# KMO_IO_MV2_9_mout.net
KiCad netlist of a schematic drawn in EAGLE
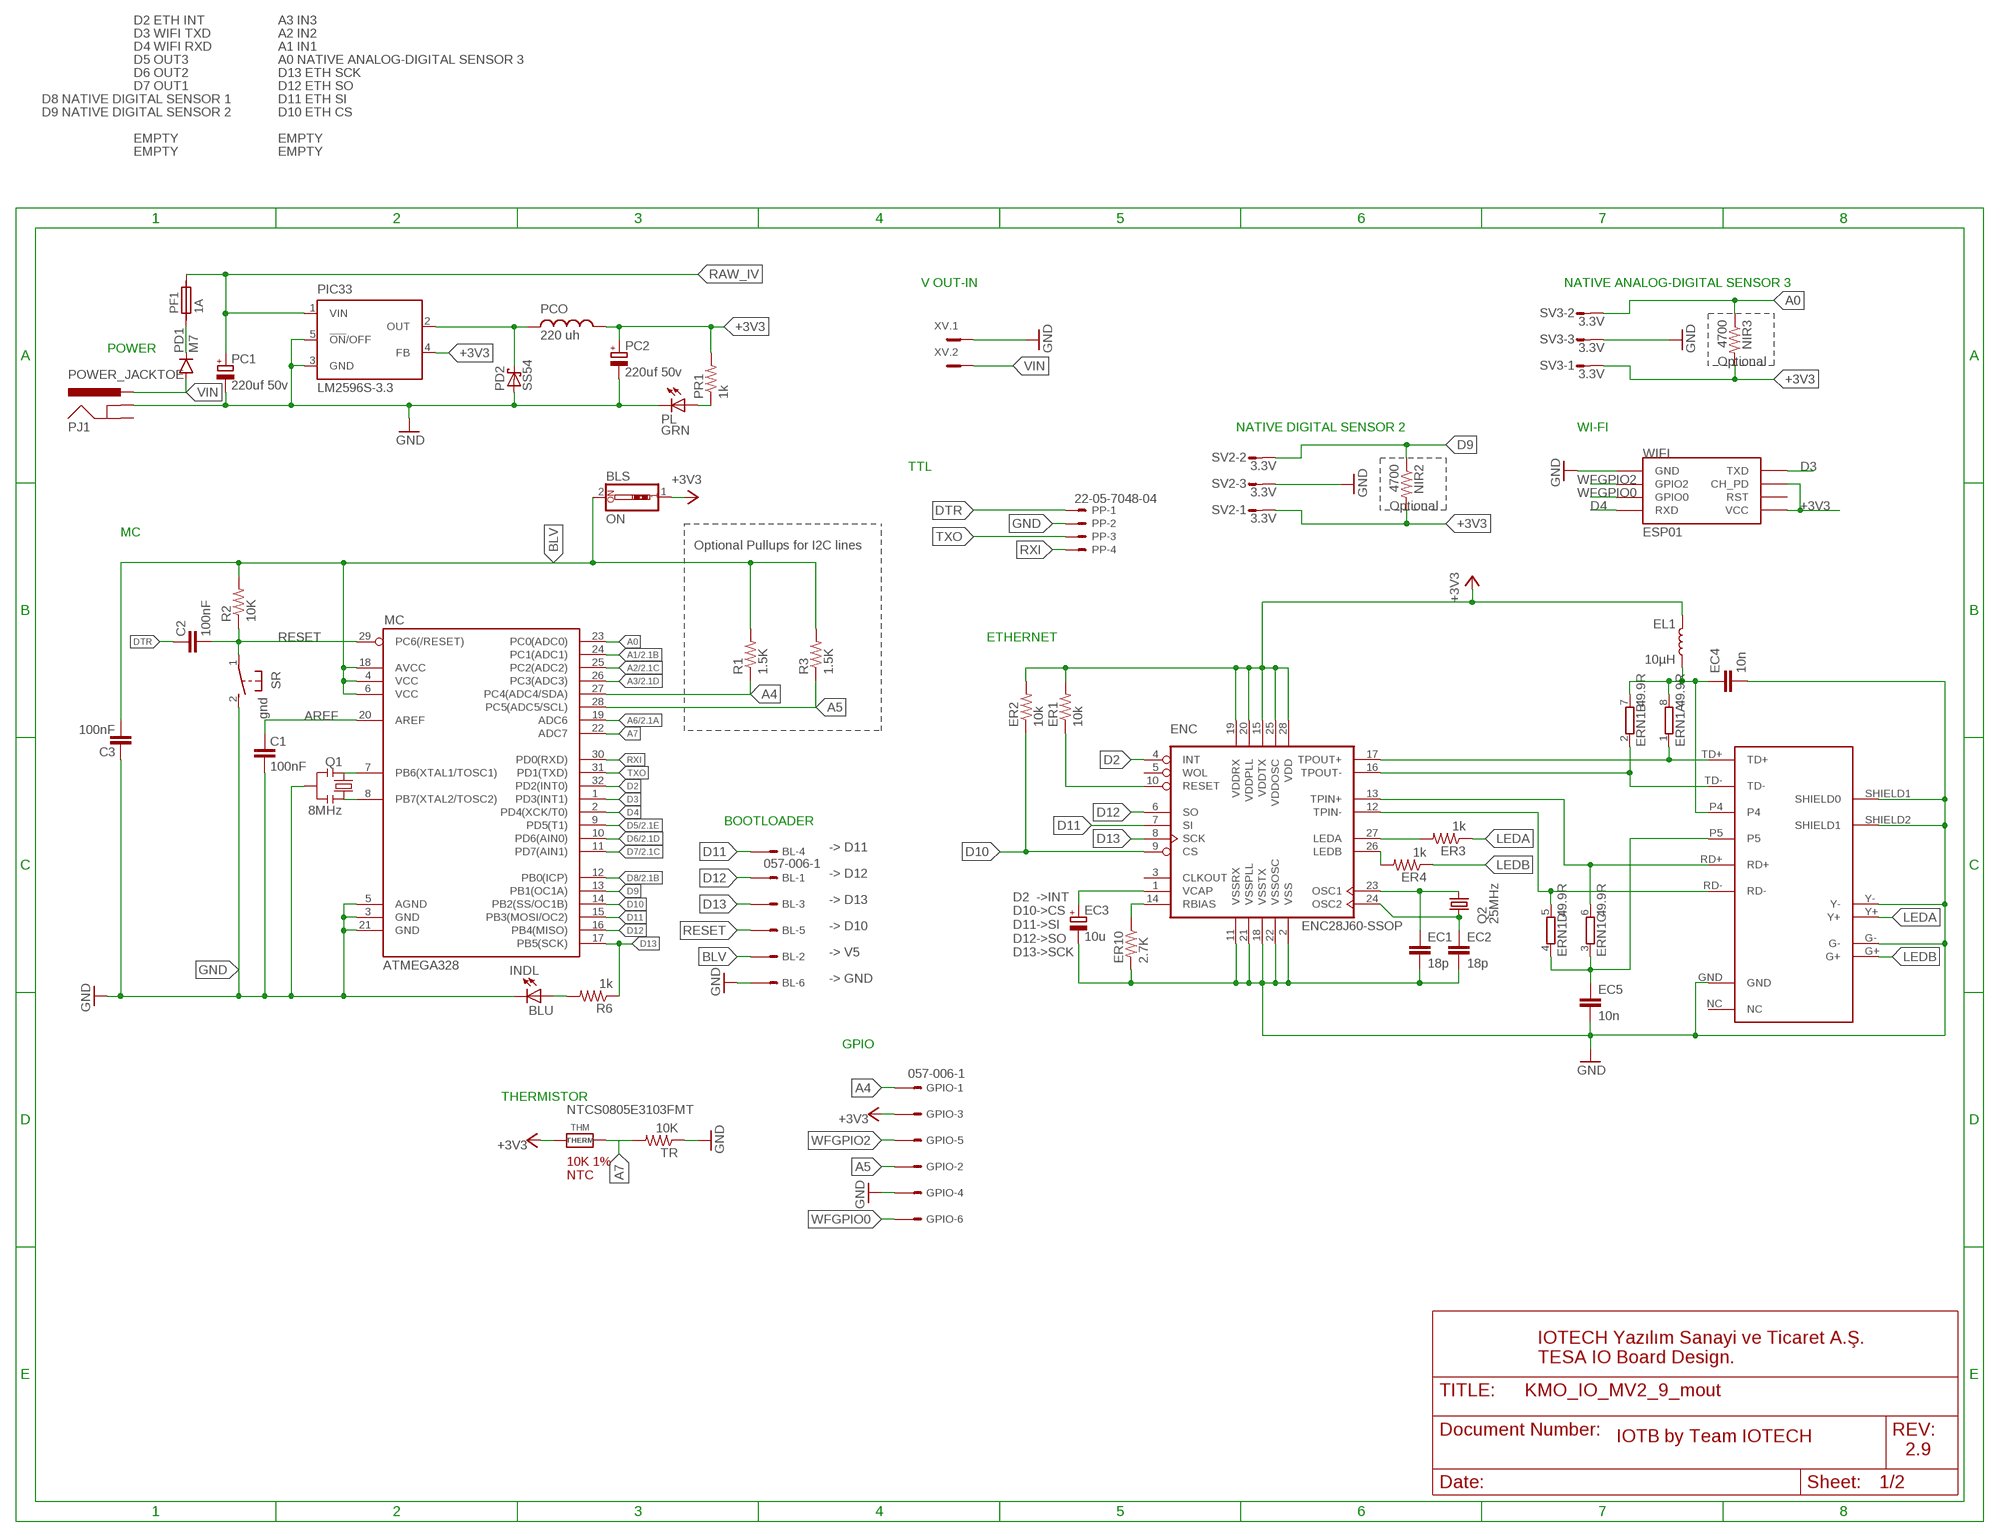
[diagram p0: schematic, sheet 1]
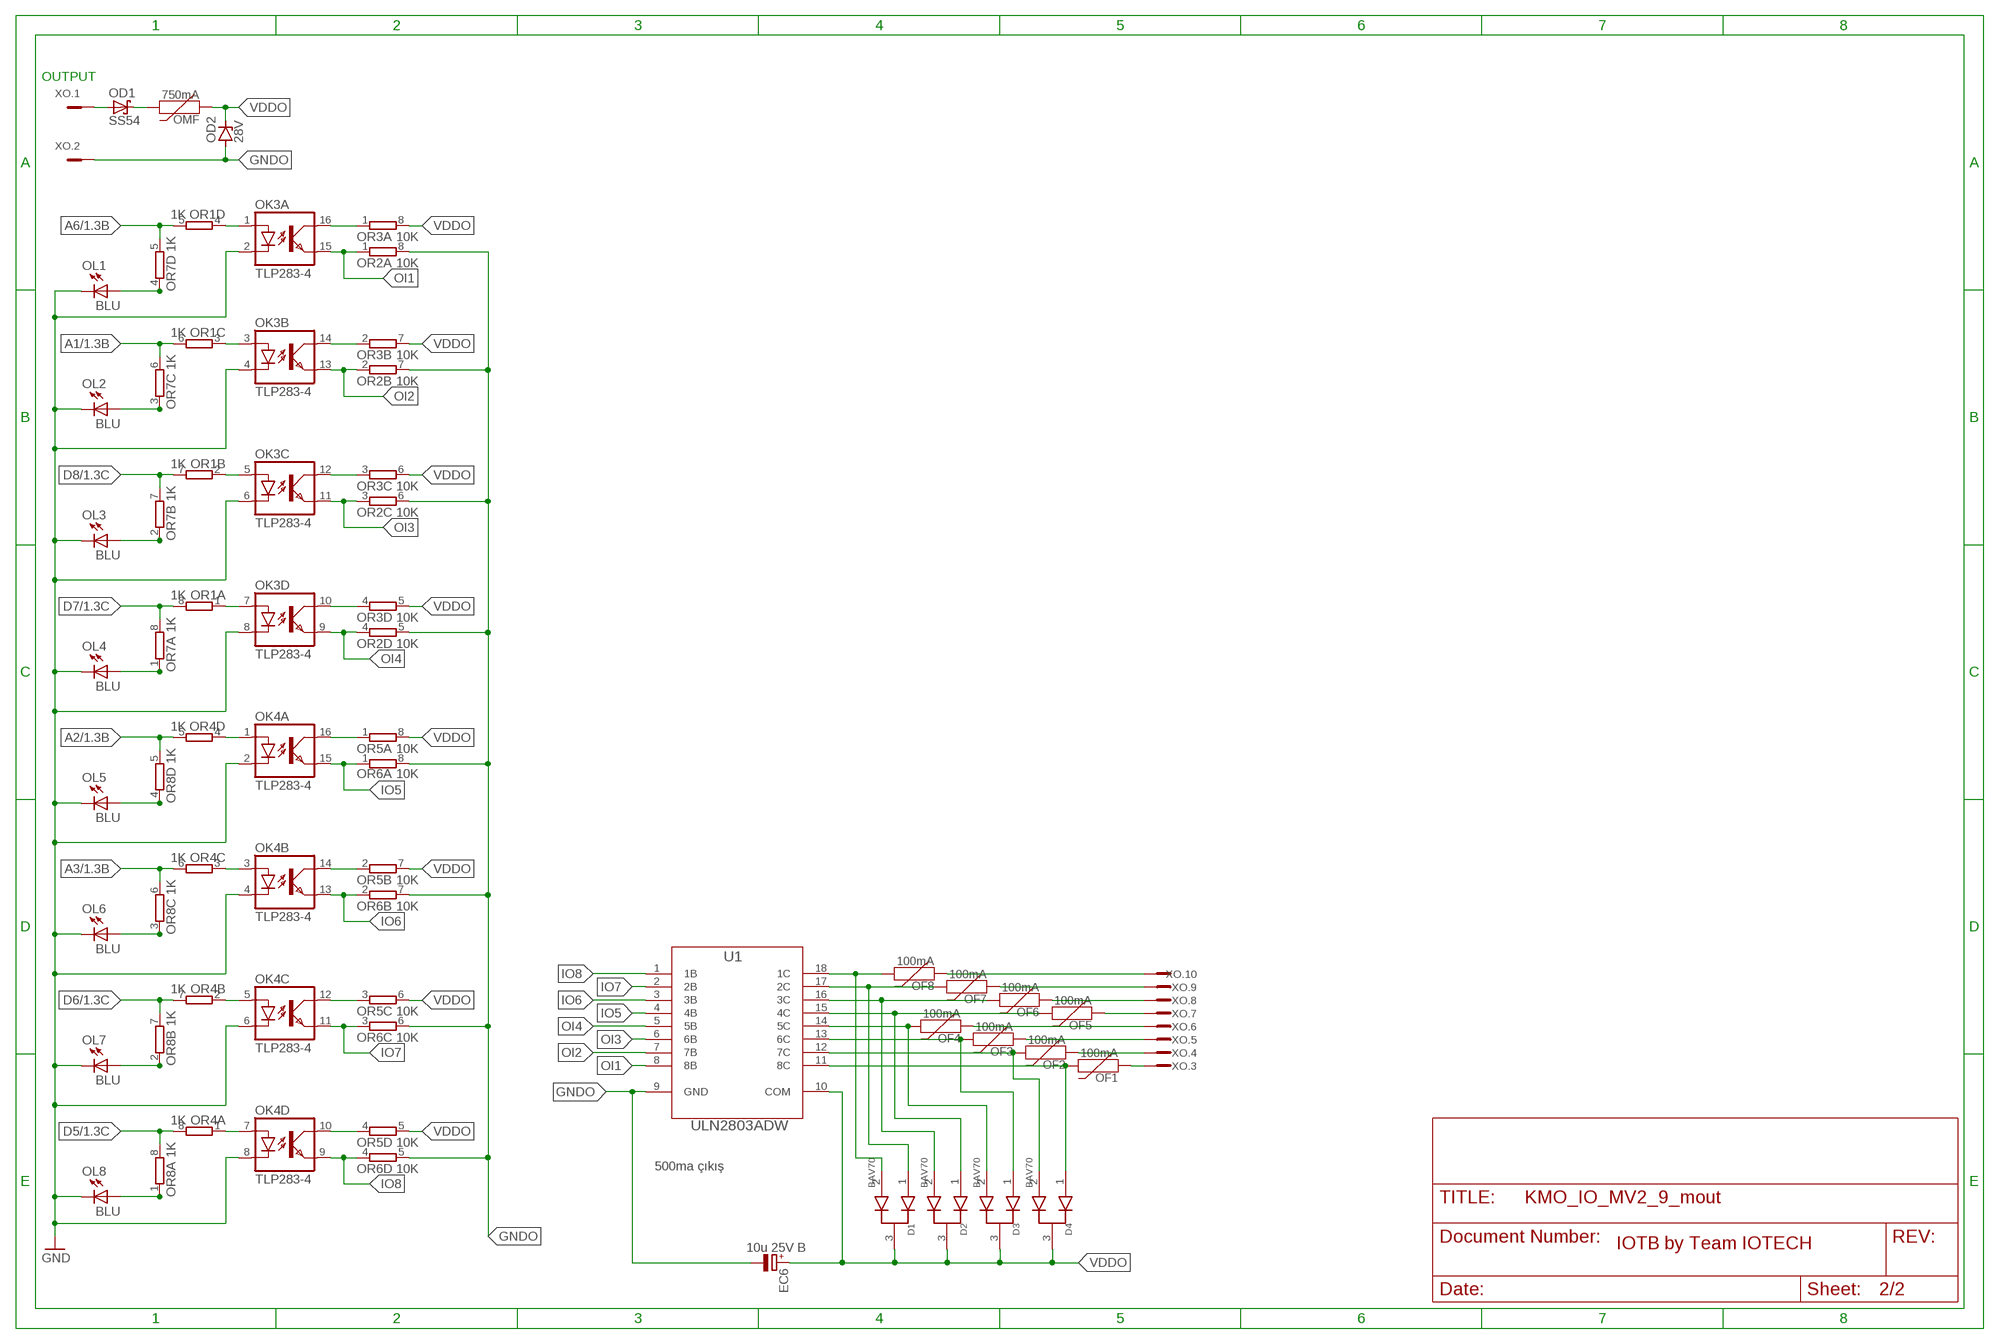
[diagram p1: schematic, sheet 2]

(export (version "E")
  (design (tool "Eeschema 10.0.6"))
  (components
    (comp (ref "BL")
      (value "057-006-1")
      (footprint "eagle-import:057-006-1")
      (libsource (lib "eagle-import") (part "057-006-1"))
    )
    (comp (ref "BLS")
      (value "ON")
      (footprint "eagle-import:EDG-01")
      (libsource (lib "eagle-import") (part "SW_DIP-1"))
    )
    (comp (ref "C1")
      (value "100nF")
      (footprint "eagle-import:0805")
      (libsource (lib "eagle-import") (part "CAP0805"))
    )
    (comp (ref "C2")
      (value "100nF")
      (footprint "eagle-import:0805")
      (libsource (lib "eagle-import") (part "CAP0805"))
    )
    (comp (ref "C3")
      (value "100nF")
      (footprint "eagle-import:0805")
      (libsource (lib "eagle-import") (part "CAP0805"))
    )
    (comp (ref "EC1")
      (value "18p")
      (footprint "eagle-import:0805")
      (libsource (lib "eagle-import") (part "CAP0805"))
    )
    (comp (ref "EC2")
      (value "18p")
      (footprint "eagle-import:0805")
      (libsource (lib "eagle-import") (part "CAP0805"))
    )
    (comp (ref "EC3")
      (value "10u")
      (footprint "eagle-import:CT3216")
      (libsource (lib "eagle-import") (part "CPOL-EUCT3216"))
    )
    (comp (ref "EC4")
      (value "10n")
      (footprint "eagle-import:0805")
      (libsource (lib "eagle-import") (part "CAP0805"))
    )
    (comp (ref "EC5")
      (value "10n")
      (footprint "eagle-import:0805")
      (libsource (lib "eagle-import") (part "CAP0805"))
    )
    (comp (ref "EL1")
      (value "10µH")
      (footprint "eagle-import:0805")
      (libsource (lib "eagle-import") (part "INDUCTOR-0805-3.3UH"))
    )
    (comp (ref "ENC")
      (value "ENC28J60-SSOP")
      (footprint "eagle-import:SSOP28")
      (libsource (lib "eagle-import") (part "ENC28J60-SSOP"))
    )
    (comp (ref "ER1")
      (value "10k")
      (footprint "eagle-import:0805")
      (libsource (lib "eagle-import") (part "RESISTOR0805-RES"))
    )
    (comp (ref "ER2")
      (value "10k")
      (footprint "eagle-import:0805")
      (libsource (lib "eagle-import") (part "RESISTOR0805-RES"))
    )
    (comp (ref "ER3")
      (value "1k")
      (footprint "eagle-import:0805")
      (libsource (lib "eagle-import") (part "RESISTOR0805-RES"))
    )
    (comp (ref "ER4")
      (value "1k")
      (footprint "eagle-import:0805")
      (libsource (lib "eagle-import") (part "RESISTOR0805-RES"))
    )
    (comp (ref "ER10")
      (value "2.7K")
      (footprint "eagle-import:0805")
      (libsource (lib "eagle-import") (part "RESISTOR0805-RES"))
    )
    (comp (ref "ERN1")
      (value "49.9R")
      (footprint "eagle-import:0603-ARV")
      (libsource (lib "eagle-import") (part "4R-N0603-ARV"))
    )
    (comp (ref "GPIO")
      (value "057-006-1")
      (footprint "eagle-import:057-006-1")
      (libsource (lib "eagle-import") (part "057-006-1"))
    )
    (comp (ref "INDL")
      (value "BLU")
      (footprint "eagle-import:CHIP-LED0805")
      (libsource (lib "eagle-import") (part "LEDCHIP-LED0805"))
    )
    (comp (ref "MC")
      (value "ATMEGA328")
      (footprint "eagle-import:TQFP32-08")
      (libsource (lib "eagle-import") (part "ATMEGA168"))
    )
    (comp (ref "NIR2")
      (value "4700")
      (footprint "eagle-import:0805")
      (libsource (lib "eagle-import") (part "RESISTOR0805-RES"))
    )
    (comp (ref "NIR3")
      (value "4700")
      (footprint "eagle-import:0805")
      (libsource (lib "eagle-import") (part "RESISTOR0805-RES"))
    )
    (comp (ref "PC1")
      (value "220uf 50v")
      (footprint "eagle-import:140CLH-1010")
      (libsource (lib "eagle-import") (part "CPOL-EU140CLH-1010"))
    )
    (comp (ref "PC2")
      (value "220uf 50v")
      (footprint "eagle-import:140CLH-1010")
      (libsource (lib "eagle-import") (part "CPOL-EU140CLH-1010"))
    )
    (comp (ref "PCO")
      (value "220 uh")
      (footprint "eagle-import:MSS1260")
      (libsource (lib "eagle-import") (part "MSS1260"))
    )
    (comp (ref "PD1")
      (value "M7")
      (footprint "eagle-import:SMA-DIODE")
      (libsource (lib "eagle-import") (part "DIODESMA"))
    )
    (comp (ref "PD2")
      (value "SS54")
      (footprint "eagle-import:SMB")
      (libsource (lib "eagle-import") (part "SCHOTTKY-DIODESMD"))
    )
    (comp (ref "PF1")
      (value "1A")
      (footprint "eagle-import:1820")
      (libsource (lib "eagle-import") (part "SIBA194600"))
    )
    (comp (ref "PIC33")
      (value "LM2596S-3.3")
      (footprint "eagle-import:TO263-5")
      (fields
        (field (name "MF") "NATIONAL SEMICONDUCTOR")
        (field (name "MPN") "LM2596S-ADJ/NOPB")
        (field (name "SPICEPREFIX") "X")
      )
      (libsource (lib "eagle-import") (part "LM2596S"))
    )
    (comp (ref "PJ1")
      (value "POWER_JACKTOE")
      (footprint "eagle-import:POWER_JACK_SMD_OVERPASTE_TOE")
      (libsource (lib "eagle-import") (part "POWER_JACKTOE"))
    )
    (comp (ref "PL")
      (value "GRN")
      (footprint "eagle-import:CHIP-LED0805")
      (libsource (lib "eagle-import") (part "LEDCHIP-LED0805"))
    )
    (comp (ref "PP")
      (value "22-05-7048-04")
      (footprint "eagle-import:7395-04")
      (fields (field (name "MF") "MOLEX"))
      (libsource (lib "eagle-import") (part "22-?-0405-7048"))
    )
    (comp (ref "PR1")
      (value "1k")
      (footprint "eagle-import:0805")
      (libsource (lib "eagle-import") (part "RESISTOR0805-RES"))
    )
    (comp (ref "Q1")
      (value "8MHz")
      (footprint "eagle-import:RESONATOR-SMD-1_1")
      (libsource (lib "eagle-import") (part "RESONATOR1{colon}1"))
    )
    (comp (ref "Q2")
      (value "25MHz")
      (footprint "eagle-import:5.0X3.2_2")
      (libsource (lib "eagle-import") (part "KX-9B"))
    )
    (comp (ref "R1")
      (value "1.5K")
      (footprint "eagle-import:0805")
      (libsource (lib "eagle-import") (part "RESISTOR0805-RES"))
    )
    (comp (ref "R2")
      (value "10K")
      (footprint "eagle-import:0805")
      (libsource (lib "eagle-import") (part "RESISTOR0805-RES"))
    )
    (comp (ref "R3")
      (value "1.5K")
      (footprint "eagle-import:0805")
      (libsource (lib "eagle-import") (part "RESISTOR0805-RES"))
    )
    (comp (ref "R6")
      (value "1k")
      (footprint "eagle-import:0805")
      (libsource (lib "eagle-import") (part "RESISTOR0805-RES"))
    )
    (comp (ref "SR")
      (value "gnd")
      (footprint "eagle-import:B3F-31XX")
      (fields (field (name "MPN") "B3F-3100"))
      (libsource (lib "eagle-import") (part "31-XX"))
    )
    (comp (ref "SV2")
      (value "3.3V")
      (footprint "eagle-import:S03P")
      (libsource (lib "eagle-import") (part "S03P"))
    )
    (comp (ref "SV3")
      (value "3.3V")
      (footprint "eagle-import:S03P")
      (libsource (lib "eagle-import") (part "S03P"))
    )
    (comp (ref "THM")
      (value "THERM")
      (footprint "eagle-import:MICROBUILDER_0805_NOTHERMALS")
      (libsource (lib "eagle-import") (part "MICROBUILDER_RESISTOR0805_NOTHERMALS"))
    )
    (comp (ref "TR")
      (value "10K")
      (footprint "eagle-import:0805")
      (libsource (lib "eagle-import") (part "RESISTOR0805-RES"))
    )
    (comp (ref "U$2")
      (value "HR911105A")
      (footprint "eagle-import:RJ45")
      (libsource (lib "eagle-import") (part "HR911105A"))
    )
    (comp (ref "WIFI")
      (value "ESP01")
      (footprint "eagle-import:ESP01")
      (libsource (lib "eagle-import") (part "ESP01"))
    )
    (comp (ref "XV")
      (value "MC2")
      (footprint "eagle-import:MC2")
      (libsource (lib "eagle-import") (part "MC2"))
    )
    (comp (ref "D1")
      (value "BAV70")
      (footprint "eagle-import:SOT-23-3")
      (fields (field (name "MF") "Multicomp") (field (name "MP") "BAV70+"))
      (libsource (lib "eagle-import") (part "BAV70"))
    )
    (comp (ref "D2")
      (value "BAV70")
      (footprint "eagle-import:SOT-23-3")
      (fields (field (name "MF") "Multicomp") (field (name "MP") "BAV70+"))
      (libsource (lib "eagle-import") (part "BAV70"))
    )
    (comp (ref "D3")
      (value "BAV70")
      (footprint "eagle-import:SOT-23-3")
      (fields (field (name "MF") "Multicomp") (field (name "MP") "BAV70+"))
      (libsource (lib "eagle-import") (part "BAV70"))
    )
    (comp (ref "D4")
      (value "BAV70")
      (footprint "eagle-import:SOT-23-3")
      (fields (field (name "MF") "Multicomp") (field (name "MP") "BAV70+"))
      (libsource (lib "eagle-import") (part "BAV70"))
    )
    (comp (ref "EC6")
      (value "10u 25V B")
      (footprint "eagle-import:SMC_B")
      (libsource (lib "eagle-import") (part "CPOL-EUSMCB"))
    )
    (comp (ref "OD1")
      (value "SS54")
      (footprint "eagle-import:SMB")
      (libsource (lib "eagle-import") (part "SCHOTTKY-DIODESMD"))
    )
    (comp (ref "OD2")
      (value "28V")
      (footprint "eagle-import:SMB")
      (libsource (lib "eagle-import") (part "ZENER-DIODESMB"))
    )
    (comp (ref "OF1")
      (value "100mA")
      (footprint "eagle-import:1206")
      (libsource (lib "eagle-import") (part "PPTC_0.75A"))
    )
    (comp (ref "OF2")
      (value "100mA")
      (footprint "eagle-import:1206")
      (libsource (lib "eagle-import") (part "PPTC_0.75A"))
    )
    (comp (ref "OF3")
      (value "100mA")
      (footprint "eagle-import:1206")
      (libsource (lib "eagle-import") (part "PPTC_0.75A"))
    )
    (comp (ref "OF4")
      (value "100mA")
      (footprint "eagle-import:1206")
      (libsource (lib "eagle-import") (part "PPTC_0.75A"))
    )
    (comp (ref "OF5")
      (value "100mA")
      (footprint "eagle-import:1206")
      (libsource (lib "eagle-import") (part "PPTC_0.75A"))
    )
    (comp (ref "OF6")
      (value "100mA")
      (footprint "eagle-import:1206")
      (libsource (lib "eagle-import") (part "PPTC_0.75A"))
    )
    (comp (ref "OF7")
      (value "100mA")
      (footprint "eagle-import:1206")
      (libsource (lib "eagle-import") (part "PPTC_0.75A"))
    )
    (comp (ref "OF8")
      (value "100mA")
      (footprint "eagle-import:1206")
      (libsource (lib "eagle-import") (part "PPTC_0.75A"))
    )
    (comp (ref "OK3")
      (value "TLP283-4")
      (footprint "eagle-import:MINI-FLAT-16")
      (libsource (lib "eagle-import") (part "TLP283-4"))
    )
    (comp (ref "OK4")
      (value "TLP283-4")
      (footprint "eagle-import:MINI-FLAT-16")
      (libsource (lib "eagle-import") (part "TLP283-4"))
    )
    (comp (ref "OL1")
      (value "BLU")
      (footprint "eagle-import:CHIP-LED0805")
      (libsource (lib "eagle-import") (part "LEDCHIP-LED0805"))
    )
    (comp (ref "OL2")
      (value "BLU")
      (footprint "eagle-import:CHIP-LED0805")
      (libsource (lib "eagle-import") (part "LEDCHIP-LED0805"))
    )
    (comp (ref "OL3")
      (value "BLU")
      (footprint "eagle-import:CHIP-LED0805")
      (libsource (lib "eagle-import") (part "LEDCHIP-LED0805"))
    )
    (comp (ref "OL4")
      (value "BLU")
      (footprint "eagle-import:CHIP-LED0805")
      (libsource (lib "eagle-import") (part "LEDCHIP-LED0805"))
    )
    (comp (ref "OL5")
      (value "BLU")
      (footprint "eagle-import:CHIP-LED0805")
      (libsource (lib "eagle-import") (part "LEDCHIP-LED0805"))
    )
    (comp (ref "OL6")
      (value "BLU")
      (footprint "eagle-import:CHIP-LED0805")
      (libsource (lib "eagle-import") (part "LEDCHIP-LED0805"))
    )
    (comp (ref "OL7")
      (value "BLU")
      (footprint "eagle-import:CHIP-LED0805")
      (libsource (lib "eagle-import") (part "LEDCHIP-LED0805"))
    )
    (comp (ref "OL8")
      (value "BLU")
      (footprint "eagle-import:CHIP-LED0805")
      (libsource (lib "eagle-import") (part "LEDCHIP-LED0805"))
    )
    (comp (ref "OMF")
      (value "750mA")
      (footprint "eagle-import:1206")
      (libsource (lib "eagle-import") (part "PPTC_0.75A"))
    )
    (comp (ref "OR1")
      (value "1K")
      (footprint "eagle-import:0603-ARV")
      (libsource (lib "eagle-import") (part "4R-N0603-ARV"))
    )
    (comp (ref "OR2")
      (value "10K")
      (footprint "eagle-import:0603-ARV")
      (libsource (lib "eagle-import") (part "4R-N0603-ARV"))
    )
    (comp (ref "OR3")
      (value "10K")
      (footprint "eagle-import:0603-ARV")
      (libsource (lib "eagle-import") (part "4R-N0603-ARV"))
    )
    (comp (ref "OR4")
      (value "1K")
      (footprint "eagle-import:0603-ARV")
      (libsource (lib "eagle-import") (part "4R-N0603-ARV"))
    )
    (comp (ref "OR5")
      (value "10K")
      (footprint "eagle-import:0603-ARV")
      (libsource (lib "eagle-import") (part "4R-N0603-ARV"))
    )
    (comp (ref "OR6")
      (value "10K")
      (footprint "eagle-import:0603-ARV")
      (libsource (lib "eagle-import") (part "4R-N0603-ARV"))
    )
    (comp (ref "OR7")
      (value "1K")
      (footprint "eagle-import:0603-ARV")
      (libsource (lib "eagle-import") (part "4R-N0603-ARV"))
    )
    (comp (ref "OR8")
      (value "1K")
      (footprint "eagle-import:0603-ARV")
      (libsource (lib "eagle-import") (part "4R-N0603-ARV"))
    )
    (comp (ref "U1")
      (value "ULN2803ADW")
      (footprint "eagle-import:SOIC127P1030X265-18N")
      (libsource (lib "eagle-import") (part "ULN2803ADW"))
    )
    (comp (ref "XO")
      (value "MC10")
      (footprint "eagle-import:MC10")
      (libsource (lib "eagle-import") (part "MC10"))
    )
  )
  (nets
    (net (code "1") (name "+3V3") (class "Default")
      (node (ref "BLS") (pin "1") (pinfunction "1_1") (pintype "passive"))
      (node (ref "EL1") (pin "1") (pinfunction "1_1") (pintype "passive"))
      (node (ref "ENC") (pin "15") (pinfunction "VDDTX_15") (pintype "power_in"))
      (node (ref "ENC") (pin "19") (pinfunction "VDDRX_19") (pintype "power_in"))
      (node (ref "ENC") (pin "20") (pinfunction "VDDPLL_20") (pintype "power_in"))
      (node (ref "ENC") (pin "25") (pinfunction "VDDOSC_25") (pintype "power_in"))
      (node (ref "ENC") (pin "28") (pinfunction "VDD_28") (pintype "power_in"))
      (node (ref "ER1") (pin "2") (pinfunction "2_2") (pintype "passive"))
      (node (ref "ER2") (pin "2") (pinfunction "2_2") (pintype "passive"))
      (node (ref "GPIO") (pin "3") (pinfunction "S_3") (pintype "passive"))
      (node (ref "NIR2") (pin "2") (pinfunction "2_2") (pintype "passive"))
      (node (ref "NIR3") (pin "2") (pinfunction "2_2") (pintype "passive"))
      (node (ref "PC2") (pin "+") (pinfunction "+_+") (pintype "passive"))
      (node (ref "PCO") (pin "P$1") (pinfunction "P$1_P$1") (pintype "passive"))
      (node (ref "PIC33") (pin "4") (pinfunction "FB_4") (pintype "input"))
      (node (ref "PR1") (pin "2") (pinfunction "2_2") (pintype "passive"))
      (node (ref "SV2") (pin "1") (pinfunction "S_1") (pintype "passive"))
      (node (ref "SV3") (pin "1") (pinfunction "S_1") (pintype "passive"))
      (node (ref "THM") (pin "1") (pinfunction "1_1") (pintype "passive"))
      (node (ref "WIFI") (pin "CH_PD") (pinfunction "CH_PD_CH_PD") (pintype "bidirectional"))
      (node (ref "WIFI") (pin "VCC") (pinfunction "VCC_VCC") (pintype "bidirectional"))
    )
    (net (code "2") (name "A0") (class "Default")
      (node (ref "MC") (pin "23") (pinfunction "PC0(ADC0)_23") (pintype "bidirectional"))
      (node (ref "NIR3") (pin "1") (pinfunction "1_1") (pintype "passive"))
      (node (ref "SV3") (pin "2") (pinfunction "S_2") (pintype "passive"))
    )
    (net (code "3") (name "A1") (class "Default")
      (node (ref "MC") (pin "24") (pinfunction "PC1(ADC1)_24") (pintype "bidirectional"))
      (node (ref "OR1") (pin "6") (pinfunction "2_6") (pintype "passive"))
      (node (ref "OR7") (pin "6") (pinfunction "2_6") (pintype "passive"))
    )
    (net (code "4") (name "A2") (class "Default")
      (node (ref "MC") (pin "25") (pinfunction "PC2(ADC2)_25") (pintype "bidirectional"))
      (node (ref "OR4") (pin "5") (pinfunction "2_5") (pintype "passive"))
      (node (ref "OR8") (pin "5") (pinfunction "2_5") (pintype "passive"))
    )
    (net (code "5") (name "A3") (class "Default")
      (node (ref "MC") (pin "26") (pinfunction "PC3(ADC3)_26") (pintype "bidirectional"))
      (node (ref "OR4") (pin "6") (pinfunction "2_6") (pintype "passive"))
      (node (ref "OR8") (pin "6") (pinfunction "2_6") (pintype "passive"))
    )
    (net (code "6") (name "A4") (class "Default")
      (node (ref "GPIO") (pin "1") (pinfunction "S_1") (pintype "passive"))
      (node (ref "MC") (pin "27") (pinfunction "PC4(ADC4/SDA)_27") (pintype "bidirectional"))
      (node (ref "R1") (pin "1") (pinfunction "1_1") (pintype "passive"))
    )
    (net (code "7") (name "A5") (class "Default")
      (node (ref "GPIO") (pin "2") (pinfunction "S_2") (pintype "passive"))
      (node (ref "MC") (pin "28") (pinfunction "PC5(ADC5/SCL)_28") (pintype "bidirectional"))
      (node (ref "R3") (pin "1") (pinfunction "1_1") (pintype "passive"))
    )
    (net (code "8") (name "A6") (class "Default")
      (node (ref "MC") (pin "19") (pinfunction "ADC6_19") (pintype "bidirectional"))
      (node (ref "OR1") (pin "5") (pinfunction "2_5") (pintype "passive"))
      (node (ref "OR7") (pin "5") (pinfunction "2_5") (pintype "passive"))
    )
    (net (code "9") (name "A7") (class "Default")
      (node (ref "MC") (pin "22") (pinfunction "ADC7_22") (pintype "bidirectional"))
      (node (ref "THM") (pin "2") (pinfunction "2_2") (pintype "passive"))
      (node (ref "TR") (pin "2") (pinfunction "2_2") (pintype "passive"))
    )
    (net (code "10") (name "AREF") (class "Default")
      (node (ref "C1") (pin "2") (pinfunction "2_2") (pintype "passive"))
      (node (ref "MC") (pin "20") (pinfunction "AREF_20") (pintype "bidirectional"))
    )
    (net (code "11") (name "BLV") (class "Default")
      (node (ref "BL") (pin "2") (pinfunction "S_2") (pintype "passive"))
      (node (ref "BLS") (pin "2") (pinfunction "2_2") (pintype "passive"))
      (node (ref "C3") (pin "1") (pinfunction "1_1") (pintype "passive"))
      (node (ref "MC") (pin "18") (pinfunction "AVCC_18") (pintype "bidirectional"))
      (node (ref "MC") (pin "4") (pinfunction "VCC_4") (pintype "bidirectional"))
      (node (ref "MC") (pin "6") (pinfunction "VCC_6") (pintype "bidirectional"))
      (node (ref "R1") (pin "2") (pinfunction "2_2") (pintype "passive"))
      (node (ref "R2") (pin "2") (pinfunction "2_2") (pintype "passive"))
      (node (ref "R3") (pin "2") (pinfunction "2_2") (pintype "passive"))
    )
    (net (code "12") (name "D2") (class "Default")
      (node (ref "ENC") (pin "4") (pinfunction "INT_4") (pintype "output"))
      (node (ref "MC") (pin "32") (pinfunction "PD2(INT0)_32") (pintype "bidirectional"))
    )
    (net (code "13") (name "D3") (class "Default")
      (node (ref "MC") (pin "1") (pinfunction "PD3(INT1)_1") (pintype "bidirectional"))
      (node (ref "WIFI") (pin "TX") (pinfunction "TXD_TX") (pintype "bidirectional"))
    )
    (net (code "14") (name "D4") (class "Default")
      (node (ref "MC") (pin "2") (pinfunction "PD4(XCK/T0)_2") (pintype "bidirectional"))
      (node (ref "WIFI") (pin "RX") (pinfunction "RXD_RX") (pintype "bidirectional"))
    )
    (net (code "15") (name "D5") (class "Default")
      (node (ref "MC") (pin "9") (pinfunction "PD5(T1)_9") (pintype "bidirectional"))
      (node (ref "OR4") (pin "8") (pinfunction "2_8") (pintype "passive"))
      (node (ref "OR8") (pin "8") (pinfunction "2_8") (pintype "passive"))
    )
    (net (code "16") (name "D6") (class "Default")
      (node (ref "MC") (pin "10") (pinfunction "PD6(AIN0)_10") (pintype "bidirectional"))
      (node (ref "OR4") (pin "7") (pinfunction "2_7") (pintype "passive"))
      (node (ref "OR8") (pin "7") (pinfunction "2_7") (pintype "passive"))
    )
    (net (code "17") (name "D7") (class "Default")
      (node (ref "MC") (pin "11") (pinfunction "PD7(AIN1)_11") (pintype "bidirectional"))
      (node (ref "OR1") (pin "8") (pinfunction "2_8") (pintype "passive"))
      (node (ref "OR7") (pin "8") (pinfunction "2_8") (pintype "passive"))
    )
    (net (code "18") (name "D8") (class "Default")
      (node (ref "MC") (pin "12") (pinfunction "PB0(ICP)_12") (pintype "bidirectional"))
      (node (ref "OR1") (pin "7") (pinfunction "2_7") (pintype "passive"))
      (node (ref "OR7") (pin "7") (pinfunction "2_7") (pintype "passive"))
    )
    (net (code "19") (name "D9") (class "Default")
      (node (ref "MC") (pin "13") (pinfunction "PB1(OC1A)_13") (pintype "bidirectional"))
      (node (ref "NIR2") (pin "1") (pinfunction "1_1") (pintype "passive"))
      (node (ref "SV2") (pin "2") (pinfunction "S_2") (pintype "passive"))
    )
    (net (code "20") (name "D10") (class "Default")
      (node (ref "ENC") (pin "9") (pinfunction "CS_9") (pintype "input"))
      (node (ref "ER2") (pin "1") (pinfunction "1_1") (pintype "passive"))
      (node (ref "MC") (pin "14") (pinfunction "PB2(SS/OC1B)_14") (pintype "bidirectional"))
    )
    (net (code "21") (name "D11") (class "Default")
      (node (ref "BL") (pin "4") (pinfunction "S_4") (pintype "passive"))
      (node (ref "ENC") (pin "7") (pinfunction "SI_7") (pintype "input"))
      (node (ref "MC") (pin "15") (pinfunction "PB3(MOSI/OC2)_15") (pintype "bidirectional"))
    )
    (net (code "22") (name "D12") (class "Default")
      (node (ref "BL") (pin "1") (pinfunction "S_1") (pintype "passive"))
      (node (ref "ENC") (pin "6") (pinfunction "SO_6") (pintype "output"))
      (node (ref "MC") (pin "16") (pinfunction "PB4(MISO)_16") (pintype "bidirectional"))
    )
    (net (code "23") (name "D13") (class "Default")
      (node (ref "BL") (pin "3") (pinfunction "S_3") (pintype "passive"))
      (node (ref "ENC") (pin "8") (pinfunction "SCK_8") (pintype "input"))
      (node (ref "MC") (pin "17") (pinfunction "PB5(SCK)_17") (pintype "bidirectional"))
      (node (ref "R6") (pin "1") (pinfunction "1_1") (pintype "passive"))
    )
    (net (code "24") (name "DTR") (class "Default")
      (node (ref "C2") (pin "2") (pinfunction "2_2") (pintype "passive"))
      (node (ref "PP") (pin "1") (pinfunction "S_1") (pintype "passive"))
    )
    (net (code "25") (name "GND") (class "Default")
      (node (ref "BL") (pin "6") (pinfunction "S_6") (pintype "passive"))
      (node (ref "C1") (pin "1") (pinfunction "1_1") (pintype "passive"))
      (node (ref "C3") (pin "2") (pinfunction "2_2") (pintype "passive"))
      (node (ref "EC1") (pin "2") (pinfunction "2_2") (pintype "passive"))
      (node (ref "EC2") (pin "2") (pinfunction "2_2") (pintype "passive"))
      (node (ref "EC3") (pin "-") (pinfunction "-_-") (pintype "passive"))
      (node (ref "EC4") (pin "2") (pinfunction "2_2") (pintype "passive"))
      (node (ref "EC5") (pin "2") (pinfunction "2_2") (pintype "passive"))
      (node (ref "ENC") (pin "11") (pinfunction "VSSRX_11") (pintype "power_in"))
      (node (ref "ENC") (pin "18") (pinfunction "VSSTX_18") (pintype "power_in"))
      (node (ref "ENC") (pin "2") (pinfunction "VSS_2") (pintype "power_in"))
      (node (ref "ENC") (pin "21") (pinfunction "VSSPLL_21") (pintype "power_in"))
      (node (ref "ENC") (pin "22") (pinfunction "VSSOSC_22") (pintype "power_in"))
      (node (ref "ER10") (pin "2") (pinfunction "2_2") (pintype "passive"))
      (node (ref "GPIO") (pin "4") (pinfunction "S_4") (pintype "passive"))
      (node (ref "INDL") (pin "C") (pinfunction "C_C") (pintype "passive"))
      (node (ref "MC") (pin "21") (pinfunction "GND_21") (pintype "bidirectional"))
      (node (ref "MC") (pin "3") (pinfunction "GND_3") (pintype "bidirectional"))
      (node (ref "MC") (pin "5") (pinfunction "AGND_5") (pintype "bidirectional"))
      (node (ref "OK3") (pin "2") (pinfunction "C_2") (pintype "passive"))
      (node (ref "OK3") (pin "4") (pinfunction "C_4") (pintype "passive"))
      (node (ref "OK3") (pin "6") (pinfunction "C_6") (pintype "passive"))
      (node (ref "OK3") (pin "8") (pinfunction "C_8") (pintype "passive"))
      (node (ref "OK4") (pin "2") (pinfunction "C_2") (pintype "passive"))
      (node (ref "OK4") (pin "4") (pinfunction "C_4") (pintype "passive"))
      (node (ref "OK4") (pin "6") (pinfunction "C_6") (pintype "passive"))
      (node (ref "OK4") (pin "8") (pinfunction "C_8") (pintype "passive"))
      (node (ref "OL1") (pin "C") (pinfunction "C_C") (pintype "passive"))
      (node (ref "OL2") (pin "C") (pinfunction "C_C") (pintype "passive"))
      (node (ref "OL3") (pin "C") (pinfunction "C_C") (pintype "passive"))
      (node (ref "OL4") (pin "C") (pinfunction "C_C") (pintype "passive"))
      (node (ref "OL5") (pin "C") (pinfunction "C_C") (pintype "passive"))
      (node (ref "OL6") (pin "C") (pinfunction "C_C") (pintype "passive"))
      (node (ref "OL7") (pin "C") (pinfunction "C_C") (pintype "passive"))
      (node (ref "OL8") (pin "C") (pinfunction "C_C") (pintype "passive"))
      (node (ref "PC1") (pin "-") (pinfunction "-_-") (pintype "passive"))
      (node (ref "PC2") (pin "-") (pinfunction "-_-") (pintype "passive"))
      (node (ref "PD2") (pin "A") (pinfunction "A_A") (pintype "passive"))
      (node (ref "PIC33") (pin "3") (pinfunction "GND_3") (pintype "power_in"))
      (node (ref "PIC33") (pin "5") (pinfunction "~{ON}/OFF_5") (pintype "input"))
      (node (ref "PJ1") (pin "GND") (pinfunction "GNDBREAK_GND") (pintype "bidirectional"))
      (node (ref "PL") (pin "C") (pinfunction "C_C") (pintype "passive"))
      (node (ref "PP") (pin "2") (pinfunction "S_2") (pintype "passive"))
      (node (ref "Q1") (pin "2") (pinfunction "2_2") (pintype "passive"))
      (node (ref "SR") (pin "2") (pinfunction "S_2") (pintype "passive"))
      (node (ref "SV2") (pin "3") (pinfunction "S_3") (pintype "passive"))
      (node (ref "SV3") (pin "3") (pinfunction "S_3") (pintype "passive"))
      (node (ref "TR") (pin "1") (pinfunction "1_1") (pintype "passive"))
      (node (ref "U$2") (pin "G-") (pinfunction "G-_G-") (pintype "bidirectional"))
      (node (ref "U$2") (pin "GND") (pinfunction "GND_GND") (pintype "bidirectional"))
      (node (ref "U$2") (pin "SHIELD1") (pinfunction "SHIELD0_SHIELD1") (pintype "bidirectional"))
      (node (ref "U$2") (pin "SHIELD2") (pinfunction "SHIELD1_SHIELD2") (pintype "bidirectional"))
      (node (ref "U$2") (pin "Y-") (pinfunction "Y-_Y-") (pintype "bidirectional"))
      (node (ref "WIFI") (pin "GND") (pinfunction "GND_GND") (pintype "bidirectional"))
      (node (ref "XV") (pin "1") (pinfunction "SK_1") (pintype "passive"))
    )
    (net (code "26") (name "GNDO") (class "Default")
      (node (ref "EC6") (pin "-") (pinfunction "-_-") (pintype "passive"))
      (node (ref "OD2") (pin "A") (pinfunction "A_A") (pintype "passive"))
      (node (ref "OR2") (pin "5") (pinfunction "2_5") (pintype "passive"))
      (node (ref "OR2") (pin "6") (pinfunction "2_6") (pintype "passive"))
      (node (ref "OR2") (pin "7") (pinfunction "2_7") (pintype "passive"))
      (node (ref "OR2") (pin "8") (pinfunction "2_8") (pintype "passive"))
      (node (ref "OR6") (pin "5") (pinfunction "2_5") (pintype "passive"))
      (node (ref "OR6") (pin "6") (pinfunction "2_6") (pintype "passive"))
      (node (ref "OR6") (pin "7") (pinfunction "2_7") (pintype "passive"))
      (node (ref "OR6") (pin "8") (pinfunction "2_8") (pintype "passive"))
      (node (ref "U1") (pin "9") (pinfunction "GND_9") (pintype "passive"))
      (node (ref "XO") (pin "2") (pinfunction "SK_2") (pintype "passive"))
    )
    (net (code "27") (name "IO5") (class "Default")
      (node (ref "OK4") (pin "15") (pinfunction "EMIT_15") (pintype "passive"))
      (node (ref "OR6") (pin "1") (pinfunction "1_1") (pintype "passive"))
      (node (ref "U1") (pin "4") (pinfunction "4B_4") (pintype "input"))
    )
    (net (code "28") (name "IO6") (class "Default")
      (node (ref "OK4") (pin "13") (pinfunction "EMIT_13") (pintype "passive"))
      (node (ref "OR6") (pin "2") (pinfunction "1_2") (pintype "passive"))
      (node (ref "U1") (pin "3") (pinfunction "3B_3") (pintype "input"))
    )
    (net (code "29") (name "IO7") (class "Default")
      (node (ref "OK4") (pin "11") (pinfunction "EMIT_11") (pintype "passive"))
      (node (ref "OR6") (pin "3") (pinfunction "1_3") (pintype "passive"))
      (node (ref "U1") (pin "2") (pinfunction "2B_2") (pintype "input"))
    )
    (net (code "30") (name "IO8") (class "Default")
      (node (ref "OK4") (pin "9") (pinfunction "EMIT_9") (pintype "passive"))
      (node (ref "OR6") (pin "4") (pinfunction "1_4") (pintype "passive"))
      (node (ref "U1") (pin "1") (pinfunction "1B_1") (pintype "input"))
    )
    (net (code "31") (name "LEDA") (class "Default")
      (node (ref "ER3") (pin "1") (pinfunction "1_1") (pintype "passive"))
      (node (ref "U$2") (pin "Y+") (pinfunction "Y+_Y+") (pintype "bidirectional"))
    )
    (net (code "32") (name "LEDB") (class "Default")
      (node (ref "ER4") (pin "1") (pinfunction "1_1") (pintype "passive"))
      (node (ref "U$2") (pin "G+") (pinfunction "G+_G+") (pintype "bidirectional"))
    )
    (net (code "33") (name "Net-(ENC-LEDA)") (class "Default")
      (node (ref "ENC") (pin "27") (pinfunction "LEDA_27") (pintype "output"))
      (node (ref "ER3") (pin "2") (pinfunction "2_2") (pintype "passive"))
    )
    (net (code "34") (name "Net-(ENC-LEDB)") (class "Default")
      (node (ref "ENC") (pin "26") (pinfunction "LEDB_26") (pintype "output"))
      (node (ref "ER4") (pin "2") (pinfunction "2_2") (pintype "passive"))
    )
    (net (code "35") (name "Net-(ENC-OSC1)") (class "Default")
      (node (ref "EC1") (pin "1") (pinfunction "1_1") (pintype "passive"))
      (node (ref "ENC") (pin "23") (pinfunction "OSC1_23") (pintype "input"))
      (node (ref "Q2") (pin "2") (pinfunction "2_2") (pintype "passive"))
    )
    (net (code "36") (name "Net-(ENC-OSC2)") (class "Default")
      (node (ref "EC2") (pin "1") (pinfunction "1_1") (pintype "passive"))
      (node (ref "ENC") (pin "24") (pinfunction "OSC2_24") (pintype "output"))
      (node (ref "Q2") (pin "1") (pinfunction "1_1") (pintype "passive"))
    )
    (net (code "37") (name "Net-(ENC-RBIAS)") (class "Default")
      (node (ref "ENC") (pin "14") (pinfunction "RBIAS_14") (pintype "passive"))
      (node (ref "ER10") (pin "1") (pinfunction "1_1") (pintype "passive"))
    )
    (net (code "38") (name "Net-(ENC-RESET)") (class "Default")
      (node (ref "ENC") (pin "10") (pinfunction "RESET_10") (pintype "input"))
      (node (ref "ER1") (pin "1") (pinfunction "1_1") (pintype "passive"))
    )
    (net (code "39") (name "Net-(ENC-TPIN+)") (class "Default")
      (node (ref "ENC") (pin "13") (pinfunction "TPIN+_13") (pintype "input"))
      (node (ref "ERN1") (pin "6") (pinfunction "2_6") (pintype "passive"))
      (node (ref "U$2") (pin "RD+") (pinfunction "RD+_RD+") (pintype "bidirectional"))
    )
    (net (code "40") (name "Net-(ENC-TPIN-)") (class "Default")
      (node (ref "ENC") (pin "12") (pinfunction "TPIN-_12") (pintype "input"))
      (node (ref "ERN1") (pin "5") (pinfunction "2_5") (pintype "passive"))
      (node (ref "U$2") (pin "RD-") (pinfunction "RD-_RD-") (pintype "bidirectional"))
    )
    (net (code "41") (name "Net-(ENC-TPOUT+)") (class "Default")
      (node (ref "ENC") (pin "17") (pinfunction "TPOUT+_17") (pintype "output"))
      (node (ref "ERN1") (pin "1") (pinfunction "1_1") (pintype "passive"))
      (node (ref "U$2") (pin "TD+") (pinfunction "TD+_TD+") (pintype "bidirectional"))
    )
    (net (code "42") (name "Net-(ENC-TPOUT-)") (class "Default")
      (node (ref "ENC") (pin "16") (pinfunction "TPOUT-_16") (pintype "output"))
      (node (ref "ERN1") (pin "2") (pinfunction "1_2") (pintype "passive"))
      (node (ref "U$2") (pin "TD-") (pinfunction "TD-_TD-") (pintype "bidirectional"))
    )
    (net (code "43") (name "Net-(ENC-VCAP)") (class "Default")
      (node (ref "EC3") (pin "+") (pinfunction "+_+") (pintype "passive"))
      (node (ref "ENC") (pin "1") (pinfunction "VCAP_1") (pintype "power_in"))
    )
    (net (code "44") (name "Net-(ERN1A-2)") (class "Default")
      (node (ref "EC4") (pin "1") (pinfunction "1_1") (pintype "passive"))
      (node (ref "EL1") (pin "2") (pinfunction "2_2") (pintype "passive"))
      (node (ref "ERN1") (pin "7") (pinfunction "2_7") (pintype "passive"))
      (node (ref "ERN1") (pin "8") (pinfunction "2_8") (pintype "passive"))
      (node (ref "U$2") (pin "P4") (pinfunction "P4_P4") (pintype "bidirectional"))
    )
    (net (code "45") (name "Net-(ERN1C-1)") (class "Default")
      (node (ref "EC5") (pin "1") (pinfunction "1_1") (pintype "passive"))
      (node (ref "ERN1") (pin "3") (pinfunction "1_3") (pintype "passive"))
      (node (ref "ERN1") (pin "4") (pinfunction "1_4") (pintype "passive"))
      (node (ref "U$2") (pin "P5") (pinfunction "P5_P5") (pintype "bidirectional"))
    )
    (net (code "46") (name "Net-(INDL-PadA)") (class "Default")
      (node (ref "INDL") (pin "A") (pinfunction "A_A") (pintype "passive"))
      (node (ref "R6") (pin "2") (pinfunction "2_2") (pintype "passive"))
    )
    (net (code "47") (name "Net-(MC-PB6(XTAL1{slash}TOSC1))") (class "Default")
      (node (ref "MC") (pin "7") (pinfunction "PB6(XTAL1/TOSC1)_7") (pintype "bidirectional"))
      (node (ref "Q1") (pin "1") (pinfunction "1_1") (pintype "passive"))
    )
    (net (code "48") (name "Net-(MC-PB7(XTAL2{slash}TOSC2))") (class "Default")
      (node (ref "MC") (pin "8") (pinfunction "PB7(XTAL2/TOSC2)_8") (pintype "bidirectional"))
      (node (ref "Q1") (pin "3") (pinfunction "3_3") (pintype "passive"))
    )
    (net (code "49") (name "Net-(OD1-PadC)") (class "Default")
      (node (ref "OD1") (pin "C") (pinfunction "C_C") (pintype "passive"))
      (node (ref "OMF") (pin "2") (pinfunction "2_2") (pintype "bidirectional"))
    )
    (net (code "50") (name "Net-(OK3A-A)") (class "Default")
      (node (ref "OK3") (pin "1") (pinfunction "A_1") (pintype "passive"))
      (node (ref "OR1") (pin "4") (pinfunction "1_4") (pintype "passive"))
    )
    (net (code "51") (name "Net-(OK3A-COL)") (class "Default")
      (node (ref "OK3") (pin "16") (pinfunction "COL_16") (pintype "passive"))
      (node (ref "OR3") (pin "1") (pinfunction "1_1") (pintype "passive"))
    )
    (net (code "52") (name "Net-(OK3B-A)") (class "Default")
      (node (ref "OK3") (pin "3") (pinfunction "A_3") (pintype "passive"))
      (node (ref "OR1") (pin "3") (pinfunction "1_3") (pintype "passive"))
    )
    (net (code "53") (name "Net-(OK3B-COL)") (class "Default")
      (node (ref "OK3") (pin "14") (pinfunction "COL_14") (pintype "passive"))
      (node (ref "OR3") (pin "2") (pinfunction "1_2") (pintype "passive"))
    )
    (net (code "54") (name "Net-(OK3C-A)") (class "Default")
      (node (ref "OK3") (pin "5") (pinfunction "A_5") (pintype "passive"))
      (node (ref "OR1") (pin "2") (pinfunction "1_2") (pintype "passive"))
    )
    (net (code "55") (name "Net-(OK3C-COL)") (class "Default")
      (node (ref "OK3") (pin "12") (pinfunction "COL_12") (pintype "passive"))
      (node (ref "OR3") (pin "3") (pinfunction "1_3") (pintype "passive"))
    )
    (net (code "56") (name "Net-(OK3D-A)") (class "Default")
      (node (ref "OK3") (pin "7") (pinfunction "A_7") (pintype "passive"))
      (node (ref "OR1") (pin "1") (pinfunction "1_1") (pintype "passive"))
    )
    (net (code "57") (name "Net-(OK3D-COL)") (class "Default")
      (node (ref "OK3") (pin "10") (pinfunction "COL_10") (pintype "passive"))
      (node (ref "OR3") (pin "4") (pinfunction "1_4") (pintype "passive"))
    )
    (net (code "58") (name "Net-(OK4A-A)") (class "Default")
      (node (ref "OK4") (pin "1") (pinfunction "A_1") (pintype "passive"))
      (node (ref "OR4") (pin "4") (pinfunction "1_4") (pintype "passive"))
    )
    (net (code "59") (name "Net-(OK4A-COL)") (class "Default")
      (node (ref "OK4") (pin "16") (pinfunction "COL_16") (pintype "passive"))
      (node (ref "OR5") (pin "1") (pinfunction "1_1") (pintype "passive"))
    )
    (net (code "60") (name "Net-(OK4B-A)") (class "Default")
      (node (ref "OK4") (pin "3") (pinfunction "A_3") (pintype "passive"))
      (node (ref "OR4") (pin "3") (pinfunction "1_3") (pintype "passive"))
    )
    (net (code "61") (name "Net-(OK4B-COL)") (class "Default")
      (node (ref "OK4") (pin "14") (pinfunction "COL_14") (pintype "passive"))
      (node (ref "OR5") (pin "2") (pinfunction "1_2") (pintype "passive"))
    )
    (net (code "62") (name "Net-(OK4C-A)") (class "Default")
      (node (ref "OK4") (pin "5") (pinfunction "A_5") (pintype "passive"))
      (node (ref "OR4") (pin "2") (pinfunction "1_2") (pintype "passive"))
    )
    (net (code "63") (name "Net-(OK4C-COL)") (class "Default")
      (node (ref "OK4") (pin "12") (pinfunction "COL_12") (pintype "passive"))
      (node (ref "OR5") (pin "3") (pinfunction "1_3") (pintype "passive"))
    )
    (net (code "64") (name "Net-(OK4D-A)") (class "Default")
      (node (ref "OK4") (pin "7") (pinfunction "A_7") (pintype "passive"))
      (node (ref "OR4") (pin "1") (pinfunction "1_1") (pintype "passive"))
    )
    (net (code "65") (name "Net-(OK4D-COL)") (class "Default")
      (node (ref "OK4") (pin "10") (pinfunction "COL_10") (pintype "passive"))
      (node (ref "OR5") (pin "4") (pinfunction "1_4") (pintype "passive"))
    )
    (net (code "66") (name "Net-(OL4-PadA)") (class "Default")
      (node (ref "OL4") (pin "A") (pinfunction "A_A") (pintype "passive"))
      (node (ref "OR7") (pin "1") (pinfunction "1_1") (pintype "passive"))
    )
    (net (code "67") (name "Net-(OL8-PadA)") (class "Default")
      (node (ref "OL8") (pin "A") (pinfunction "A_A") (pintype "passive"))
      (node (ref "OR8") (pin "1") (pinfunction "1_1") (pintype "passive"))
    )
    (net (code "68") (name "Net-(OR7B-1)") (class "Default")
      (node (ref "OL3") (pin "A") (pinfunction "A_A") (pintype "passive"))
      (node (ref "OR7") (pin "2") (pinfunction "1_2") (pintype "passive"))
    )
    (net (code "69") (name "Net-(OR7C-1)") (class "Default")
      (node (ref "OL2") (pin "A") (pinfunction "A_A") (pintype "passive"))
      (node (ref "OR7") (pin "3") (pinfunction "1_3") (pintype "passive"))
    )
    (net (code "70") (name "Net-(OR7D-1)") (class "Default")
      (node (ref "OL1") (pin "A") (pinfunction "A_A") (pintype "passive"))
      (node (ref "OR7") (pin "4") (pinfunction "1_4") (pintype "passive"))
    )
    (net (code "71") (name "Net-(OR8B-1)") (class "Default")
      (node (ref "OL7") (pin "A") (pinfunction "A_A") (pintype "passive"))
      (node (ref "OR8") (pin "2") (pinfunction "1_2") (pintype "passive"))
    )
    (net (code "72") (name "Net-(OR8C-1)") (class "Default")
      (node (ref "OL6") (pin "A") (pinfunction "A_A") (pintype "passive"))
      (node (ref "OR8") (pin "3") (pinfunction "1_3") (pintype "passive"))
    )
    (net (code "73") (name "Net-(OR8D-1)") (class "Default")
      (node (ref "OL5") (pin "A") (pinfunction "A_A") (pintype "passive"))
      (node (ref "OR8") (pin "4") (pinfunction "1_4") (pintype "passive"))
    )
    (net (code "74") (name "Net-(PD1-PadC)") (class "Default")
      (node (ref "PD1") (pin "C") (pinfunction "C_C") (pintype "passive"))
      (node (ref "PF1") (pin "1") (pinfunction "1_1") (pintype "passive"))
    )
    (net (code "75") (name "Net-(PIC33-OUT)") (class "Default")
      (node (ref "PCO") (pin "P$2") (pinfunction "P$2_P$2") (pintype "passive"))
      (node (ref "PD2") (pin "C") (pinfunction "C_C") (pintype "passive"))
      (node (ref "PIC33") (pin "2") (pinfunction "OUT_2") (pintype "output"))
    )
    (net (code "76") (name "Net-(PL-PadA)") (class "Default")
      (node (ref "PL") (pin "A") (pinfunction "A_A") (pintype "passive"))
      (node (ref "PR1") (pin "1") (pinfunction "1_1") (pintype "passive"))
    )
    (net (code "77") (name "Net-(U1-1C)") (class "Default")
      (node (ref "D1") (pin "2") (pinfunction "2_2") (pintype "bidirectional"))
      (node (ref "OF8") (pin "2") (pinfunction "2_2") (pintype "bidirectional"))
      (node (ref "U1") (pin "18") (pinfunction "1C_18") (pintype "output"))
    )
    (net (code "78") (name "Net-(U1-2C)") (class "Default")
      (node (ref "D1") (pin "1") (pinfunction "1_1") (pintype "bidirectional"))
      (node (ref "OF7") (pin "2") (pinfunction "2_2") (pintype "bidirectional"))
      (node (ref "U1") (pin "17") (pinfunction "2C_17") (pintype "output"))
    )
    (net (code "79") (name "Net-(U1-3C)") (class "Default")
      (node (ref "D2") (pin "2") (pinfunction "2_2") (pintype "bidirectional"))
      (node (ref "OF6") (pin "2") (pinfunction "2_2") (pintype "bidirectional"))
      (node (ref "U1") (pin "16") (pinfunction "3C_16") (pintype "output"))
    )
    (net (code "80") (name "Net-(U1-4C)") (class "Default")
      (node (ref "D2") (pin "1") (pinfunction "1_1") (pintype "bidirectional"))
      (node (ref "OF5") (pin "2") (pinfunction "2_2") (pintype "bidirectional"))
      (node (ref "U1") (pin "15") (pinfunction "4C_15") (pintype "output"))
    )
    (net (code "81") (name "Net-(U1-5C)") (class "Default")
      (node (ref "D3") (pin "2") (pinfunction "2_2") (pintype "bidirectional"))
      (node (ref "OF4") (pin "2") (pinfunction "2_2") (pintype "bidirectional"))
      (node (ref "U1") (pin "14") (pinfunction "5C_14") (pintype "output"))
    )
    (net (code "82") (name "Net-(U1-6C)") (class "Default")
      (node (ref "D3") (pin "1") (pinfunction "1_1") (pintype "bidirectional"))
      (node (ref "OF3") (pin "2") (pinfunction "2_2") (pintype "bidirectional"))
      (node (ref "U1") (pin "13") (pinfunction "6C_13") (pintype "output"))
    )
    (net (code "83") (name "Net-(U1-7C)") (class "Default")
      (node (ref "D4") (pin "2") (pinfunction "2_2") (pintype "bidirectional"))
      (node (ref "OF2") (pin "2") (pinfunction "2_2") (pintype "bidirectional"))
      (node (ref "U1") (pin "12") (pinfunction "7C_12") (pintype "output"))
    )
    (net (code "84") (name "Net-(U1-8C)") (class "Default")
      (node (ref "D4") (pin "1") (pinfunction "1_1") (pintype "bidirectional"))
      (node (ref "OF1") (pin "2") (pinfunction "2_2") (pintype "bidirectional"))
      (node (ref "U1") (pin "11") (pinfunction "8C_11") (pintype "output"))
    )
    (net (code "85") (name "Net-(XOA-SK)") (class "Default")
      (node (ref "OD1") (pin "A") (pinfunction "A_A") (pintype "passive"))
      (node (ref "XO") (pin "1") (pinfunction "SK_1") (pintype "passive"))
    )
    (net (code "86") (name "Net-(XOB-SK)") (class "Default")
      (node (ref "OF8") (pin "1") (pinfunction "1_1") (pintype "bidirectional"))
      (node (ref "XO") (pin "10") (pinfunction "SK_10") (pintype "passive"))
    )
    (net (code "87") (name "Net-(XOD-SK)") (class "Default")
      (node (ref "OF1") (pin "1") (pinfunction "1_1") (pintype "bidirectional"))
      (node (ref "XO") (pin "3") (pinfunction "SK_3") (pintype "passive"))
    )
    (net (code "88") (name "Net-(XOE-SK)") (class "Default")
      (node (ref "OF2") (pin "1") (pinfunction "1_1") (pintype "bidirectional"))
      (node (ref "XO") (pin "4") (pinfunction "SK_4") (pintype "passive"))
    )
    (net (code "89") (name "Net-(XOF-SK)") (class "Default")
      (node (ref "OF3") (pin "1") (pinfunction "1_1") (pintype "bidirectional"))
      (node (ref "XO") (pin "5") (pinfunction "SK_5") (pintype "passive"))
    )
    (net (code "90") (name "Net-(XOG-SK)") (class "Default")
      (node (ref "OF4") (pin "1") (pinfunction "1_1") (pintype "bidirectional"))
      (node (ref "XO") (pin "6") (pinfunction "SK_6") (pintype "passive"))
    )
    (net (code "91") (name "Net-(XOH-SK)") (class "Default")
      (node (ref "OF5") (pin "1") (pinfunction "1_1") (pintype "bidirectional"))
      (node (ref "XO") (pin "7") (pinfunction "SK_7") (pintype "passive"))
    )
    (net (code "92") (name "Net-(XOI-SK)") (class "Default")
      (node (ref "OF6") (pin "1") (pinfunction "1_1") (pintype "bidirectional"))
      (node (ref "XO") (pin "8") (pinfunction "SK_8") (pintype "passive"))
    )
    (net (code "93") (name "Net-(XOJ-SK)") (class "Default")
      (node (ref "OF7") (pin "1") (pinfunction "1_1") (pintype "bidirectional"))
      (node (ref "XO") (pin "9") (pinfunction "SK_9") (pintype "passive"))
    )
    (net (code "94") (name "OI1") (class "Default")
      (node (ref "OK3") (pin "15") (pinfunction "EMIT_15") (pintype "passive"))
      (node (ref "OR2") (pin "1") (pinfunction "1_1") (pintype "passive"))
      (node (ref "U1") (pin "8") (pinfunction "8B_8") (pintype "input"))
    )
    (net (code "95") (name "OI2") (class "Default")
      (node (ref "OK3") (pin "13") (pinfunction "EMIT_13") (pintype "passive"))
      (node (ref "OR2") (pin "2") (pinfunction "1_2") (pintype "passive"))
      (node (ref "U1") (pin "7") (pinfunction "7B_7") (pintype "input"))
    )
    (net (code "96") (name "OI3") (class "Default")
      (node (ref "OK3") (pin "11") (pinfunction "EMIT_11") (pintype "passive"))
      (node (ref "OR2") (pin "3") (pinfunction "1_3") (pintype "passive"))
      (node (ref "U1") (pin "6") (pinfunction "6B_6") (pintype "input"))
    )
    (net (code "97") (name "OI4") (class "Default")
      (node (ref "OK3") (pin "9") (pinfunction "EMIT_9") (pintype "passive"))
      (node (ref "OR2") (pin "4") (pinfunction "1_4") (pintype "passive"))
      (node (ref "U1") (pin "5") (pinfunction "5B_5") (pintype "input"))
    )
    (net (code "98") (name "RAW_IV") (class "Default")
      (node (ref "PC1") (pin "+") (pinfunction "+_+") (pintype "passive"))
      (node (ref "PF1") (pin "2") (pinfunction "2_2") (pintype "passive"))
      (node (ref "PIC33") (pin "1") (pinfunction "VIN_1") (pintype "input"))
    )
    (net (code "99") (name "RESET") (class "Default")
      (node (ref "BL") (pin "5") (pinfunction "S_5") (pintype "passive"))
      (node (ref "C2") (pin "1") (pinfunction "1_1") (pintype "passive"))
      (node (ref "MC") (pin "29") (pinfunction "PC6(/RESET)_29") (pintype "bidirectional"))
      (node (ref "R2") (pin "1") (pinfunction "1_1") (pintype "passive"))
      (node (ref "SR") (pin "1") (pinfunction "P_1") (pintype "passive"))
    )
    (net (code "100") (name "RXI") (class "Default")
      (node (ref "MC") (pin "30") (pinfunction "PD0(RXD)_30") (pintype "bidirectional"))
      (node (ref "PP") (pin "4") (pinfunction "S_4") (pintype "passive"))
    )
    (net (code "101") (name "TXO") (class "Default")
      (node (ref "MC") (pin "31") (pinfunction "PD1(TXD)_31") (pintype "bidirectional"))
      (node (ref "PP") (pin "3") (pinfunction "S_3") (pintype "passive"))
    )
    (net (code "102") (name "VDDO") (class "Default")
      (node (ref "D1") (pin "3") (pinfunction "3_3") (pintype "bidirectional"))
      (node (ref "D2") (pin "3") (pinfunction "3_3") (pintype "bidirectional"))
      (node (ref "D3") (pin "3") (pinfunction "3_3") (pintype "bidirectional"))
      (node (ref "D4") (pin "3") (pinfunction "3_3") (pintype "bidirectional"))
      (node (ref "EC6") (pin "+") (pinfunction "+_+") (pintype "passive"))
      (node (ref "OD2") (pin "C") (pinfunction "C_C") (pintype "passive"))
      (node (ref "OMF") (pin "1") (pinfunction "1_1") (pintype "bidirectional"))
      (node (ref "OR3") (pin "5") (pinfunction "2_5") (pintype "passive"))
      (node (ref "OR3") (pin "6") (pinfunction "2_6") (pintype "passive"))
      (node (ref "OR3") (pin "7") (pinfunction "2_7") (pintype "passive"))
      (node (ref "OR3") (pin "8") (pinfunction "2_8") (pintype "passive"))
      (node (ref "OR5") (pin "5") (pinfunction "2_5") (pintype "passive"))
      (node (ref "OR5") (pin "6") (pinfunction "2_6") (pintype "passive"))
      (node (ref "OR5") (pin "7") (pinfunction "2_7") (pintype "passive"))
      (node (ref "OR5") (pin "8") (pinfunction "2_8") (pintype "passive"))
      (node (ref "U1") (pin "10") (pinfunction "COM_10") (pintype "output"))
    )
    (net (code "103") (name "VIN") (class "Default")
      (node (ref "PD1") (pin "A") (pinfunction "A_A") (pintype "passive"))
      (node (ref "PJ1") (pin "VIN0") (pinfunction "PWR_VIN0") (pintype "bidirectional"))
      (node (ref "XV") (pin "2") (pinfunction "SK_2") (pintype "passive"))
    )
    (net (code "104") (name "WFGPIO0") (class "Default")
      (node (ref "GPIO") (pin "6") (pinfunction "S_6") (pintype "passive"))
      (node (ref "WIFI") (pin "GPIO0") (pinfunction "GPIO0_GPIO0") (pintype "bidirectional"))
    )
    (net (code "105") (name "WFGPIO2") (class "Default")
      (node (ref "GPIO") (pin "5") (pinfunction "S_5") (pintype "passive"))
      (node (ref "WIFI") (pin "GPIO2") (pinfunction "GPIO2_GPIO2") (pintype "bidirectional"))
    )
    (net (code "106") (name "unconnected-(ENC-CLKOUT-Pad3)") (class "Default")
      (node (ref "ENC") (pin "3") (pinfunction "CLKOUT_3") (pintype "output"))
    )
    (net (code "107") (name "unconnected-(ENC-WOL-Pad5)") (class "Default")
      (node (ref "ENC") (pin "5") (pinfunction "WOL_5") (pintype "output"))
    )
    (net (code "108") (name "unconnected-(PJ1-GND-PadP$4)") (class "Default")
      (node (ref "PJ1") (pin "P$4") (pinfunction "GND_P$4") (pintype "bidirectional"))
    )
    (net (code "109") (name "unconnected-(U$2-PadNC)") (class "Default")
      (node (ref "U$2") (pin "NC") (pinfunction "NC_NC") (pintype "bidirectional"))
    )
    (net (code "110") (name "unconnected-(WIFI-PadRST)") (class "Default")
      (node (ref "WIFI") (pin "RST") (pinfunction "RST_RST") (pintype "bidirectional"))
    )
  )
)
